# gospboard-v1.net
KiCad netlist of a schematic drawn in EAGLE
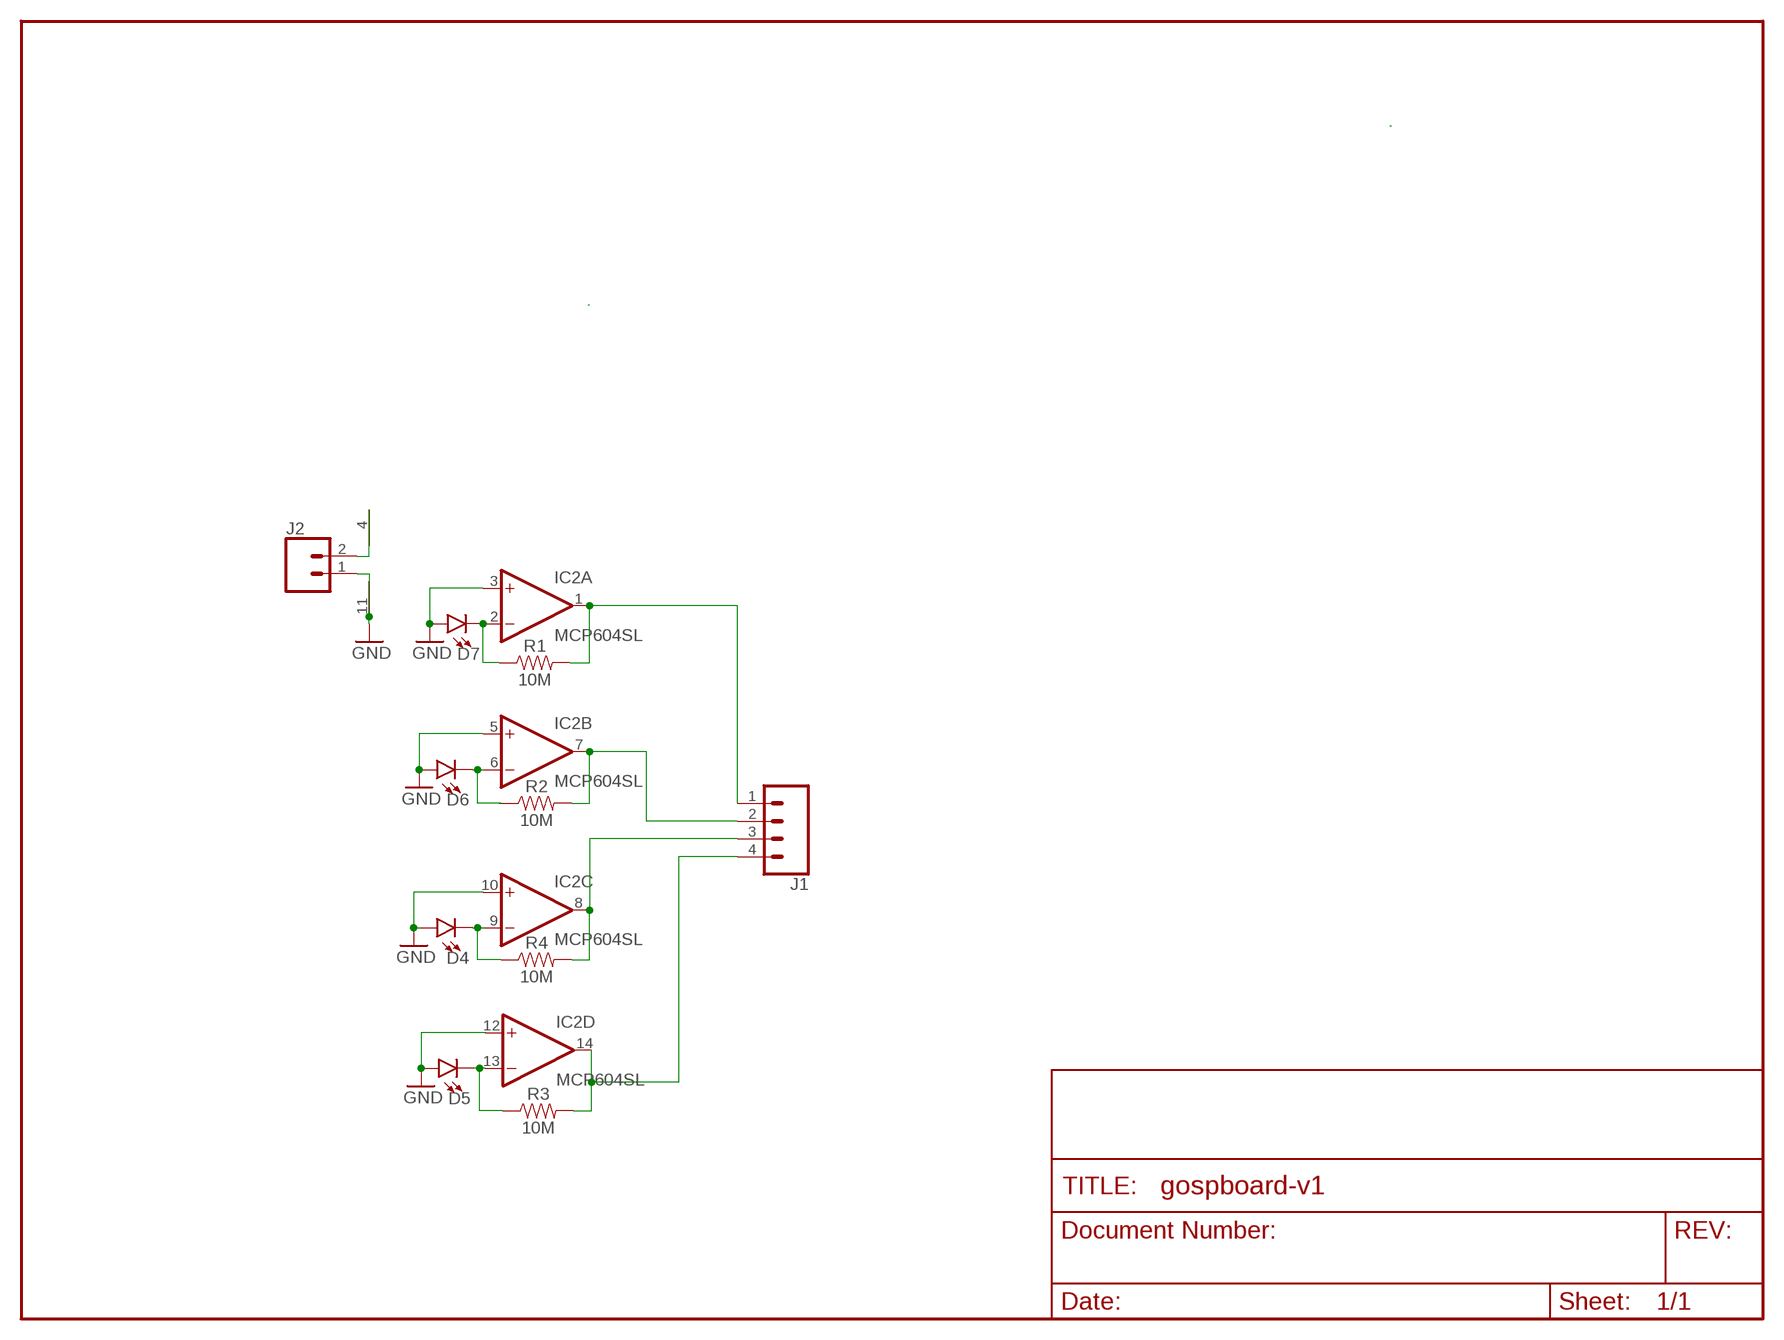
[diagram p0: schematic, sheet 1]

(export (version "E")
  (design (tool "Eeschema 10.0.6"))
  (components
    (comp (ref "D4")
      (value "LED3MM")
      (footprint "eagle-import:LED_3MM")
      (libsource (lib "eagle-import") (part "LED3MM"))
    )
    (comp (ref "D5")
      (value "LED3MM")
      (footprint "eagle-import:LED_3MM")
      (libsource (lib "eagle-import") (part "LED3MM"))
    )
    (comp (ref "D6")
      (value "LED3MM")
      (footprint "eagle-import:LED_3MM")
      (libsource (lib "eagle-import") (part "LED3MM"))
    )
    (comp (ref "D7")
      (value "LED3MM")
      (footprint "eagle-import:LED_3MM")
      (libsource (lib "eagle-import") (part "LED3MM"))
    )
    (comp (ref "IC2")
      (value "MCP604SL")
      (footprint "eagle-import:SO14")
      (libsource (lib "eagle-import") (part "MCP604SL"))
    )
    (comp (ref "J1")
      (value "CONN_04")
      (footprint "eagle-import:1X04")
      (libsource (lib "eagle-import") (part "CONN_04"))
    )
    (comp (ref "J2")
      (value "CONN_02")
      (footprint "eagle-import:1X02")
      (libsource (lib "eagle-import") (part "CONN_02"))
    )
    (comp (ref "R1")
      (value "10M")
      (footprint "eagle-import:0603")
      (libsource (lib "eagle-import") (part "1MOHM-0603-1/4W-5%"))
    )
    (comp (ref "R2")
      (value "10M")
      (footprint "eagle-import:0603")
      (libsource (lib "eagle-import") (part "1MOHM-0603-1/4W-5%"))
    )
    (comp (ref "R3")
      (value "10M")
      (footprint "eagle-import:0603")
      (libsource (lib "eagle-import") (part "1MOHM-0603-1/4W-5%"))
    )
    (comp (ref "R4")
      (value "10M")
      (footprint "eagle-import:0603")
      (libsource (lib "eagle-import") (part "1MOHM-0603-1/4W-5%"))
    )
  )
  (nets
    (net (code "1") (name "GND") (class "Default")
      (node (ref "D4") (pin "A") (pinfunction "A_A") (pintype "passive"))
      (node (ref "D5") (pin "A") (pinfunction "A_A") (pintype "passive"))
      (node (ref "D6") (pin "A") (pinfunction "A_A") (pintype "passive"))
      (node (ref "D7") (pin "A") (pinfunction "A_A") (pintype "passive"))
      (node (ref "IC2") (pin "10") (pinfunction "+IN_10") (pintype "input"))
      (node (ref "IC2") (pin "11") (pinfunction "V-_11") (pintype "power_in"))
      (node (ref "IC2") (pin "12") (pinfunction "+IN_12") (pintype "input"))
      (node (ref "IC2") (pin "3") (pinfunction "+IN_3") (pintype "input"))
      (node (ref "IC2") (pin "5") (pinfunction "+IN_5") (pintype "input"))
      (node (ref "J2") (pin "1") (pinfunction "1_1") (pintype "passive"))
    )
    (net (code "2") (name "Net-(D4-C)") (class "Default")
      (node (ref "D4") (pin "K") (pinfunction "C_K") (pintype "passive"))
      (node (ref "IC2") (pin "9") (pinfunction "-IN_9") (pintype "input"))
      (node (ref "R4") (pin "1") (pinfunction "1_1") (pintype "passive"))
    )
    (net (code "3") (name "Net-(D5-C)") (class "Default")
      (node (ref "D5") (pin "K") (pinfunction "C_K") (pintype "passive"))
      (node (ref "IC2") (pin "13") (pinfunction "-IN_13") (pintype "input"))
      (node (ref "R3") (pin "1") (pinfunction "1_1") (pintype "passive"))
    )
    (net (code "4") (name "Net-(D6-C)") (class "Default")
      (node (ref "D6") (pin "K") (pinfunction "C_K") (pintype "passive"))
      (node (ref "IC2") (pin "6") (pinfunction "-IN_6") (pintype "input"))
      (node (ref "R2") (pin "1") (pinfunction "1_1") (pintype "passive"))
    )
    (net (code "5") (name "Net-(D7-C)") (class "Default")
      (node (ref "D7") (pin "K") (pinfunction "C_K") (pintype "passive"))
      (node (ref "IC2") (pin "2") (pinfunction "-IN_2") (pintype "input"))
      (node (ref "R1") (pin "1") (pinfunction "1_1") (pintype "passive"))
    )
    (net (code "6") (name "Net-(IC2A-OUT)") (class "Default")
      (node (ref "IC2") (pin "1") (pinfunction "OUT_1") (pintype "output"))
      (node (ref "J1") (pin "1") (pinfunction "1_1") (pintype "passive"))
      (node (ref "R1") (pin "2") (pinfunction "2_2") (pintype "passive"))
    )
    (net (code "7") (name "Net-(IC2B-OUT)") (class "Default")
      (node (ref "IC2") (pin "7") (pinfunction "OUT_7") (pintype "output"))
      (node (ref "J1") (pin "2") (pinfunction "2_2") (pintype "passive"))
      (node (ref "R2") (pin "2") (pinfunction "2_2") (pintype "passive"))
    )
    (net (code "8") (name "Net-(IC2C-OUT)") (class "Default")
      (node (ref "IC2") (pin "8") (pinfunction "OUT_8") (pintype "output"))
      (node (ref "J1") (pin "3") (pinfunction "3_3") (pintype "passive"))
      (node (ref "R4") (pin "2") (pinfunction "2_2") (pintype "passive"))
    )
    (net (code "9") (name "Net-(IC2D-OUT)") (class "Default")
      (node (ref "IC2") (pin "14") (pinfunction "OUT_14") (pintype "output"))
      (node (ref "J1") (pin "4") (pinfunction "4_4") (pintype "passive"))
      (node (ref "R3") (pin "2") (pinfunction "2_2") (pintype "passive"))
    )
    (net (code "10") (name "Net-(IC2E-V+)") (class "Default")
      (node (ref "IC2") (pin "4") (pinfunction "V+_4") (pintype "power_in"))
      (node (ref "J2") (pin "2") (pinfunction "2_2") (pintype "passive"))
    )
  )
)
